# routev3_2.net
KiCad netlist of a schematic drawn in EAGLE
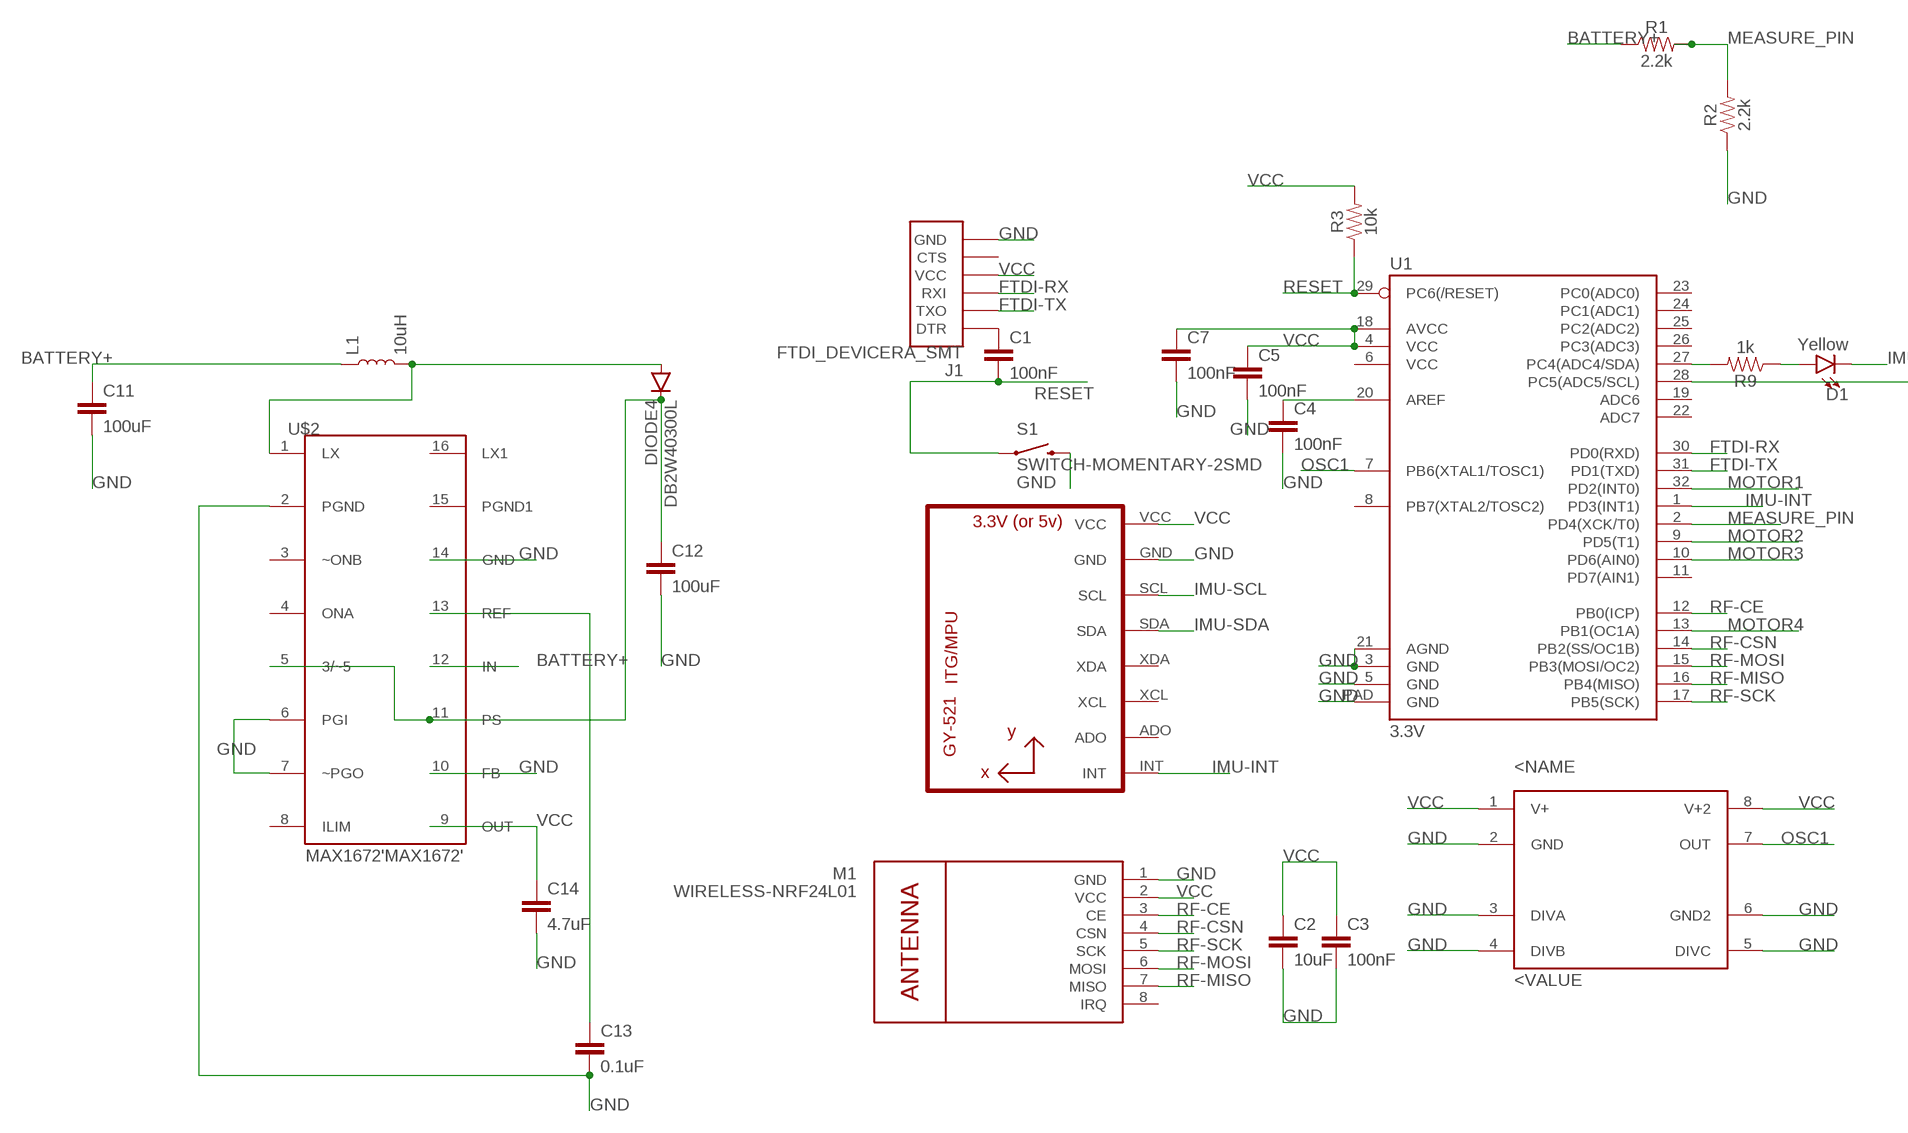
[diagram p0: schematic, sheet 1, part 1 of 2]
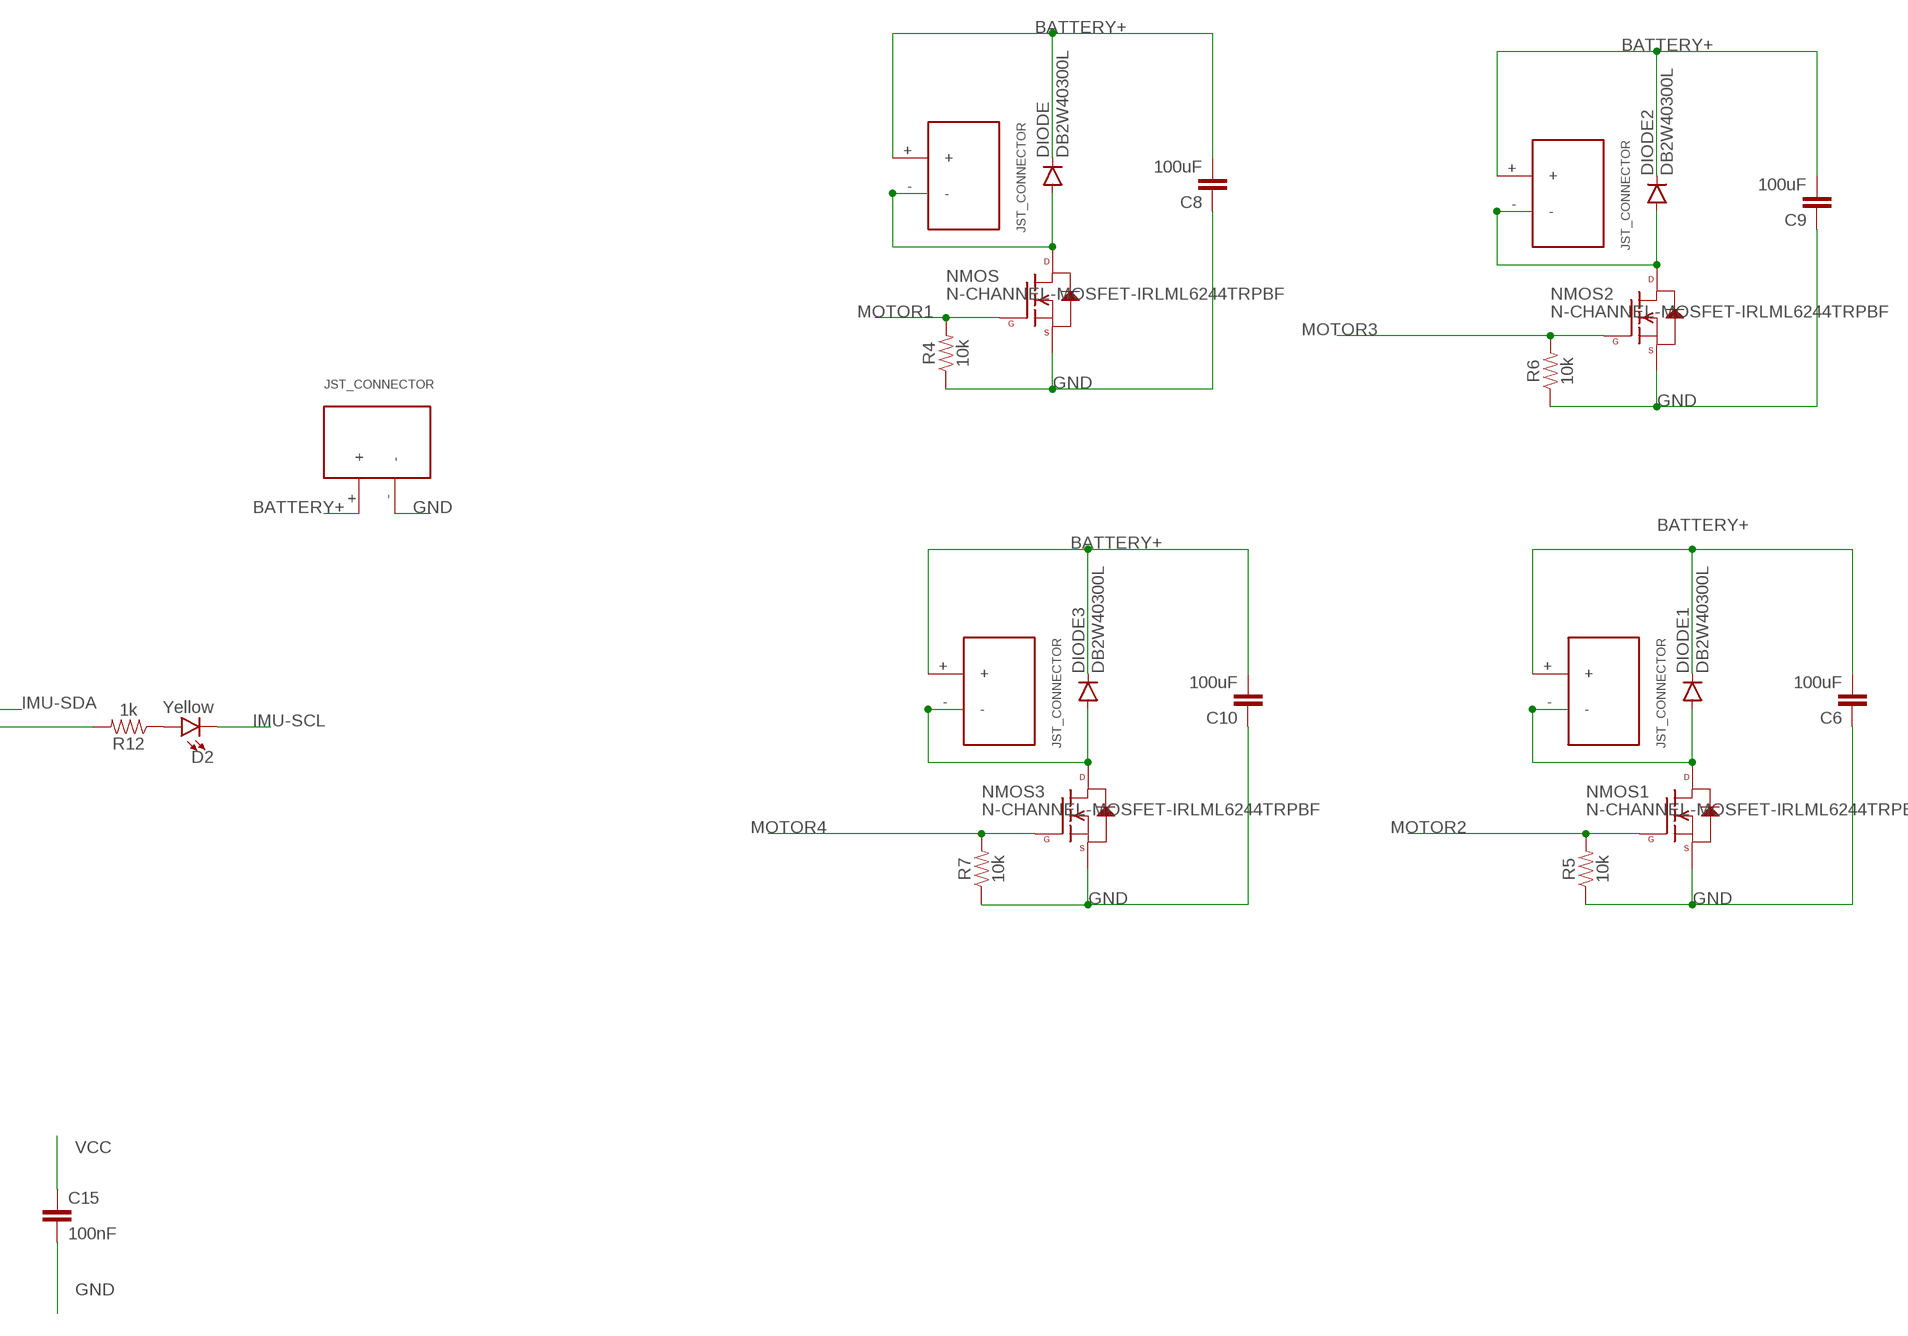
[diagram p1: schematic, sheet 1, part 2 of 2]

(export (version "E")
  (design (tool "Eeschema 10.0.6"))
  (components
    (comp (ref "C1")
      (value "100nF")
      (footprint "eagle-import:0603-CAP")
      (libsource (lib "eagle-import") (part "0.1UF-25V(+80/-20%)(0603)"))
    )
    (comp (ref "C2")
      (value "10uF")
      (footprint "eagle-import:0603-CAP")
      (libsource (lib "eagle-import") (part "CAP0603-CAP"))
    )
    (comp (ref "C3")
      (value "100nF")
      (footprint "eagle-import:0603-CAP")
      (libsource (lib "eagle-import") (part "CAP0603-CAP"))
    )
    (comp (ref "C4")
      (value "100nF")
      (footprint "eagle-import:0603-CAP")
      (libsource (lib "eagle-import") (part "CAP0603-CAP"))
    )
    (comp (ref "C5")
      (value "100nF")
      (footprint "eagle-import:0603-CAP")
      (libsource (lib "eagle-import") (part "CAP0603-CAP"))
    )
    (comp (ref "C6")
      (value "100uF")
      (footprint "eagle-import:0603-CAP")
      (libsource (lib "eagle-import") (part "CAP0603-CAP"))
    )
    (comp (ref "C7")
      (value "100nF")
      (footprint "eagle-import:0603-CAP")
      (libsource (lib "eagle-import") (part "CAP0603-CAP"))
    )
    (comp (ref "C8")
      (value "100uF")
      (footprint "eagle-import:0603-CAP")
      (libsource (lib "eagle-import") (part "CAP0603-CAP"))
    )
    (comp (ref "C9")
      (value "100uF")
      (footprint "eagle-import:0603-CAP")
      (libsource (lib "eagle-import") (part "CAP0603-CAP"))
    )
    (comp (ref "C10")
      (value "100uF")
      (footprint "eagle-import:0603-CAP")
      (libsource (lib "eagle-import") (part "CAP0603-CAP"))
    )
    (comp (ref "C11")
      (value "100uF")
      (footprint "eagle-import:0603-CAP")
      (libsource (lib "eagle-import") (part "CAP0603-CAP"))
    )
    (comp (ref "C12")
      (value "100uF")
      (footprint "eagle-import:0603-CAP")
      (libsource (lib "eagle-import") (part "CAP0603-CAP"))
    )
    (comp (ref "C13")
      (value "0.1uF")
      (footprint "eagle-import:0603-CAP")
      (libsource (lib "eagle-import") (part "CAP0603-CAP"))
    )
    (comp (ref "C14")
      (value "4.7uF")
      (footprint "eagle-import:0603-CAP")
      (libsource (lib "eagle-import") (part "CAP0603-CAP"))
    )
    (comp (ref "C15")
      (value "100nF")
      (footprint "eagle-import:0603-CAP")
      (libsource (lib "eagle-import") (part "0.1UF-25V(+80/-20%)(0603)"))
    )
    (comp (ref "D1")
      (value "Yellow")
      (footprint "eagle-import:LED-1206")
      (libsource (lib "eagle-import") (part "LED-YELLOWLILYPAD"))
    )
    (comp (ref "D2")
      (value "Yellow")
      (footprint "eagle-import:LED-1206")
      (libsource (lib "eagle-import") (part "LED-YELLOWLILYPAD"))
    )
    (comp (ref "DIODE")
      (value "DB2W40300L")
      (footprint "eagle-import:MINI2-F3-B")
      (libsource (lib "eagle-import") (part "DB2W40300L"))
    )
    (comp (ref "DIODE1")
      (value "DB2W40300L")
      (footprint "eagle-import:MINI2-F3-B")
      (libsource (lib "eagle-import") (part "DB2W40300L"))
    )
    (comp (ref "DIODE2")
      (value "DB2W40300L")
      (footprint "eagle-import:MINI2-F3-B")
      (libsource (lib "eagle-import") (part "DB2W40300L"))
    )
    (comp (ref "DIODE3")
      (value "DB2W40300L")
      (footprint "eagle-import:MINI2-F3-B")
      (libsource (lib "eagle-import") (part "DB2W40300L"))
    )
    (comp (ref "DIODE4")
      (value "DB2W40300L")
      (footprint "eagle-import:MINI2-F3-B")
      (libsource (lib "eagle-import") (part "DB2W40300L"))
    )
    (comp (ref "J1")
      (value "FTDI_DEVICERA_SMT")
      (footprint "eagle-import:FTDI_DEVICE_RA_SMT")
      (libsource (lib "eagle-import") (part "FTDI_DEVICERA_SMT"))
    )
    (comp (ref "L1")
      (value "10uH")
      (footprint "eagle-import:0603")
      (libsource (lib "eagle-import") (part "INDUCTOR-0603-33NH"))
    )
    (comp (ref "M1")
      (value "WIRELESS-NRF24L01")
      (footprint "eagle-import:WIRELESS-NRF24L01")
      (libsource (lib "eagle-import") (part "WIRELESS-NRF24L01"))
    )
    (comp (ref "MOTOR")
      (value "JST_CONNECTOR_FEMALE")
      (footprint "eagle-import:JST_CONNECTOR_FEMALE")
      (libsource (lib "eagle-import") (part "JST_CONNECTOR_FEMALE"))
    )
    (comp (ref "MOTOR1")
      (value "JST_CONNECTOR_FEMALE")
      (footprint "eagle-import:JST_CONNECTOR_FEMALE")
      (libsource (lib "eagle-import") (part "JST_CONNECTOR_FEMALE"))
    )
    (comp (ref "MOTOR2")
      (value "JST_CONNECTOR_FEMALE")
      (footprint "eagle-import:JST_CONNECTOR_FEMALE")
      (libsource (lib "eagle-import") (part "JST_CONNECTOR_FEMALE"))
    )
    (comp (ref "MOTOR3")
      (value "JST_CONNECTOR_FEMALE")
      (footprint "eagle-import:JST_CONNECTOR_FEMALE")
      (libsource (lib "eagle-import") (part "JST_CONNECTOR_FEMALE"))
    )
    (comp (ref "NMOS")
      (value "N-CHANNEL-MOSFET-IRLML6244TRPBF")
      (footprint "eagle-import:SOT23-3")
      (libsource (lib "eagle-import") (part "N-CHANNEL-MOSFET-IRLML6244TRPBF"))
    )
    (comp (ref "NMOS1")
      (value "N-CHANNEL-MOSFET-IRLML6244TRPBF")
      (footprint "eagle-import:SOT23-3")
      (libsource (lib "eagle-import") (part "N-CHANNEL-MOSFET-IRLML6244TRPBF"))
    )
    (comp (ref "NMOS2")
      (value "N-CHANNEL-MOSFET-IRLML6244TRPBF")
      (footprint "eagle-import:SOT23-3")
      (libsource (lib "eagle-import") (part "N-CHANNEL-MOSFET-IRLML6244TRPBF"))
    )
    (comp (ref "NMOS3")
      (value "N-CHANNEL-MOSFET-IRLML6244TRPBF")
      (footprint "eagle-import:SOT23-3")
      (libsource (lib "eagle-import") (part "N-CHANNEL-MOSFET-IRLML6244TRPBF"))
    )
    (comp (ref "R1")
      (value "2.2k")
      (footprint "eagle-import:0603")
      (libsource (lib "eagle-import") (part "2.2KOHM-0603-1/10W-1%"))
    )
    (comp (ref "R2")
      (value "2.2k")
      (footprint "eagle-import:0603")
      (libsource (lib "eagle-import") (part "2.2KOHM-0603-1/10W-1%"))
    )
    (comp (ref "R3")
      (value "10k")
      (footprint "eagle-import:0603")
      (libsource (lib "eagle-import") (part "2.2KOHM-0603-1/10W-1%"))
    )
    (comp (ref "R4")
      (value "10k")
      (footprint "eagle-import:0603")
      (libsource (lib "eagle-import") (part "2.2KOHM-0603-1/10W-1%"))
    )
    (comp (ref "R5")
      (value "10k")
      (footprint "eagle-import:0603")
      (libsource (lib "eagle-import") (part "2.2KOHM-0603-1/10W-1%"))
    )
    (comp (ref "R6")
      (value "10k")
      (footprint "eagle-import:0603")
      (libsource (lib "eagle-import") (part "2.2KOHM-0603-1/10W-1%"))
    )
    (comp (ref "R7")
      (value "10k")
      (footprint "eagle-import:0603")
      (libsource (lib "eagle-import") (part "2.2KOHM-0603-1/10W-1%"))
    )
    (comp (ref "R9")
      (value "1k")
      (footprint "eagle-import:0603")
      (libsource (lib "eagle-import") (part "2.2KOHM-0603-1/10W-1%"))
    )
    (comp (ref "R12")
      (value "1k")
      (footprint "eagle-import:0603")
      (libsource (lib "eagle-import") (part "2.2KOHM-0603-1/10W-1%"))
    )
    (comp (ref "S1")
      (value "SWITCH-MOMENTARY-2SMD")
      (footprint "eagle-import:TACTILE-SWITCH-SMD")
      (libsource (lib "eagle-import") (part "SWITCH-MOMENTARY-2SMD"))
    )
    (comp (ref "U$1")
      (value "JST_CONNECTOR_FEMALE")
      (footprint "eagle-import:JST_CONNECTOR_FEMALE")
      (libsource (lib "eagle-import") (part "JST_CONNECTOR_FEMALE"))
    )
    (comp (ref "U$2")
      (value "MAX1672'MAX1672'")
      (footprint "eagle-import:21-0055H_16")
      (libsource (lib "eagle-import") (part "MAX1672'MAX1672'"))
    )
    (comp (ref "U$3")
      (value "LTC6930CMS8-8.19LTC6930CMS8-8.19")
      (footprint "eagle-import:SOP65P490X110-8N")
      (libsource (lib "eagle-import") (part "LTC6930CMS8-8.19LTC6930CMS8-8.19"))
    )
    (comp (ref "U1")
      (value "3.3V")
      (footprint "eagle-import:MLF32-PAD")
      (libsource (lib "eagle-import") (part "ATMEGA328P_MLFMLF32"))
    )
    (comp (ref "U2")
      (value "GY-521MPU6050")
      (footprint "eagle-import:GY-521")
      (libsource (lib "eagle-import") (part "GY-521MPU6050"))
    )
  )
  (nets
    (net (code "1") (name "BATTERY+") (class "Default")
      (node (ref "C10") (pin "2") (pinfunction "2_2") (pintype "passive"))
      (node (ref "C11") (pin "1") (pinfunction "1_1") (pintype "passive"))
      (node (ref "C6") (pin "2") (pinfunction "2_2") (pintype "passive"))
      (node (ref "C8") (pin "2") (pinfunction "2_2") (pintype "passive"))
      (node (ref "C9") (pin "2") (pinfunction "2_2") (pintype "passive"))
      (node (ref "DIODE") (pin "NEG") (pinfunction "GPIN_NEG") (pintype "passive"))
      (node (ref "DIODE1") (pin "NEG") (pinfunction "GPIN_NEG") (pintype "passive"))
      (node (ref "DIODE2") (pin "NEG") (pinfunction "GPIN_NEG") (pintype "passive"))
      (node (ref "DIODE3") (pin "NEG") (pinfunction "GPIN_NEG") (pintype "passive"))
      (node (ref "L1") (pin "1") (pinfunction "1_1") (pintype "passive"))
      (node (ref "MOTOR") (pin "+") (pinfunction "+_+") (pintype "bidirectional"))
      (node (ref "MOTOR1") (pin "+") (pinfunction "+_+") (pintype "bidirectional"))
      (node (ref "MOTOR2") (pin "+") (pinfunction "+_+") (pintype "bidirectional"))
      (node (ref "MOTOR3") (pin "+") (pinfunction "+_+") (pintype "bidirectional"))
      (node (ref "R1") (pin "1") (pinfunction "1_1") (pintype "passive"))
      (node (ref "U$1") (pin "+") (pinfunction "+_+") (pintype "bidirectional"))
      (node (ref "U$2") (pin "12") (pinfunction "IN_12") (pintype "bidirectional"))
    )
    (net (code "2") (name "FTDI-RX") (class "Default")
      (node (ref "J1") (pin "3") (pinfunction "RXI_3") (pintype "bidirectional"))
      (node (ref "U1") (pin "30") (pinfunction "PD0(RXD)_30") (pintype "bidirectional"))
    )
    (net (code "3") (name "FTDI-TX") (class "Default")
      (node (ref "J1") (pin "2") (pinfunction "TXO_2") (pintype "bidirectional"))
      (node (ref "U1") (pin "31") (pinfunction "PD1(TXD)_31") (pintype "bidirectional"))
    )
    (net (code "4") (name "GND") (class "Default")
      (node (ref "C10") (pin "1") (pinfunction "1_1") (pintype "passive"))
      (node (ref "C11") (pin "2") (pinfunction "2_2") (pintype "passive"))
      (node (ref "C12") (pin "2") (pinfunction "2_2") (pintype "passive"))
      (node (ref "C13") (pin "2") (pinfunction "2_2") (pintype "passive"))
      (node (ref "C14") (pin "2") (pinfunction "2_2") (pintype "passive"))
      (node (ref "C15") (pin "2") (pinfunction "2_2") (pintype "passive"))
      (node (ref "C2") (pin "2") (pinfunction "2_2") (pintype "passive"))
      (node (ref "C3") (pin "2") (pinfunction "2_2") (pintype "passive"))
      (node (ref "C4") (pin "2") (pinfunction "2_2") (pintype "passive"))
      (node (ref "C5") (pin "2") (pinfunction "2_2") (pintype "passive"))
      (node (ref "C6") (pin "1") (pinfunction "1_1") (pintype "passive"))
      (node (ref "C7") (pin "2") (pinfunction "2_2") (pintype "passive"))
      (node (ref "C8") (pin "1") (pinfunction "1_1") (pintype "passive"))
      (node (ref "C9") (pin "1") (pinfunction "1_1") (pintype "passive"))
      (node (ref "J1") (pin "6") (pinfunction "GND_6") (pintype "bidirectional"))
      (node (ref "M1") (pin "1") (pinfunction "GND_1") (pintype "power_in"))
      (node (ref "NMOS") (pin "2") (pinfunction "S_2") (pintype "passive"))
      (node (ref "NMOS1") (pin "2") (pinfunction "S_2") (pintype "passive"))
      (node (ref "NMOS2") (pin "2") (pinfunction "S_2") (pintype "passive"))
      (node (ref "NMOS3") (pin "2") (pinfunction "S_2") (pintype "passive"))
      (node (ref "R2") (pin "1") (pinfunction "1_1") (pintype "passive"))
      (node (ref "R4") (pin "1") (pinfunction "1_1") (pintype "passive"))
      (node (ref "R5") (pin "1") (pinfunction "1_1") (pintype "passive"))
      (node (ref "R6") (pin "1") (pinfunction "1_1") (pintype "passive"))
      (node (ref "R7") (pin "1") (pinfunction "1_1") (pintype "passive"))
      (node (ref "S1") (pin "3") (pinfunction "2_3") (pintype "passive"))
      (node (ref "U$1") (pin "-") (pinfunction "-_-") (pintype "bidirectional"))
      (node (ref "U$2") (pin "10") (pinfunction "FB_10") (pintype "bidirectional"))
      (node (ref "U$2") (pin "14") (pinfunction "GND_14") (pintype "bidirectional"))
      (node (ref "U$2") (pin "2") (pinfunction "PGND_2") (pintype "bidirectional"))
      (node (ref "U$2") (pin "6") (pinfunction "PGI_6") (pintype "bidirectional"))
      (node (ref "U$2") (pin "7") (pinfunction "~{PGO}_7") (pintype "bidirectional"))
      (node (ref "U$3") (pin "2") (pinfunction "GND_2") (pintype "bidirectional"))
      (node (ref "U$3") (pin "3") (pinfunction "DIVA_3") (pintype "bidirectional"))
      (node (ref "U$3") (pin "4") (pinfunction "DIVB_4") (pintype "bidirectional"))
      (node (ref "U$3") (pin "5") (pinfunction "DIVC_5") (pintype "bidirectional"))
      (node (ref "U$3") (pin "6") (pinfunction "GND2_6") (pintype "bidirectional"))
      (node (ref "U1") (pin "21") (pinfunction "AGND_21") (pintype "bidirectional"))
      (node (ref "U1") (pin "3") (pinfunction "GND_3") (pintype "bidirectional"))
      (node (ref "U1") (pin "5") (pinfunction "GND_5") (pintype "bidirectional"))
      (node (ref "U1") (pin "PAD") (pinfunction "GND_PAD") (pintype "bidirectional"))
      (node (ref "U2") (pin "GND") (pinfunction "GND_GND") (pintype "bidirectional"))
    )
    (net (code "5") (name "IMU-INT") (class "Default")
      (node (ref "U1") (pin "1") (pinfunction "PD3(INT1)_1") (pintype "bidirectional"))
      (node (ref "U2") (pin "INT") (pinfunction "INT_INT") (pintype "bidirectional"))
    )
    (net (code "6") (name "IMU-SCL") (class "Default")
      (node (ref "D2") (pin "C") (pinfunction "C_C") (pintype "passive"))
      (node (ref "U2") (pin "SCL") (pinfunction "SCL_SCL") (pintype "bidirectional"))
    )
    (net (code "7") (name "IMU-SDA") (class "Default")
      (node (ref "D1") (pin "C") (pinfunction "C_C") (pintype "passive"))
      (node (ref "U2") (pin "SDA") (pinfunction "SDA_SDA") (pintype "bidirectional"))
    )
    (net (code "8") (name "MEASURE_PIN") (class "Default")
      (node (ref "R1") (pin "2") (pinfunction "2_2") (pintype "passive"))
      (node (ref "R2") (pin "2") (pinfunction "2_2") (pintype "passive"))
      (node (ref "U1") (pin "2") (pinfunction "PD4(XCK/T0)_2") (pintype "bidirectional"))
    )
    (net (code "9") (name "MOTOR1") (class "Default")
      (node (ref "NMOS") (pin "1") (pinfunction "G_1") (pintype "passive"))
      (node (ref "R4") (pin "2") (pinfunction "2_2") (pintype "passive"))
      (node (ref "U1") (pin "32") (pinfunction "PD2(INT0)_32") (pintype "bidirectional"))
    )
    (net (code "10") (name "MOTOR2") (class "Default")
      (node (ref "NMOS1") (pin "1") (pinfunction "G_1") (pintype "passive"))
      (node (ref "R5") (pin "2") (pinfunction "2_2") (pintype "passive"))
      (node (ref "U1") (pin "9") (pinfunction "PD5(T1)_9") (pintype "bidirectional"))
    )
    (net (code "11") (name "MOTOR3") (class "Default")
      (node (ref "NMOS2") (pin "1") (pinfunction "G_1") (pintype "passive"))
      (node (ref "R6") (pin "2") (pinfunction "2_2") (pintype "passive"))
      (node (ref "U1") (pin "10") (pinfunction "PD6(AIN0)_10") (pintype "bidirectional"))
    )
    (net (code "12") (name "MOTOR4") (class "Default")
      (node (ref "NMOS3") (pin "1") (pinfunction "G_1") (pintype "passive"))
      (node (ref "R7") (pin "2") (pinfunction "2_2") (pintype "passive"))
      (node (ref "U1") (pin "13") (pinfunction "PB1(OC1A)_13") (pintype "bidirectional"))
    )
    (net (code "13") (name "Net-(D1-PadA)") (class "Default")
      (node (ref "D1") (pin "A") (pinfunction "A_A") (pintype "passive"))
      (node (ref "R9") (pin "1") (pinfunction "1_1") (pintype "passive"))
    )
    (net (code "14") (name "Net-(D2-PadA)") (class "Default")
      (node (ref "D2") (pin "A") (pinfunction "A_A") (pintype "passive"))
      (node (ref "R12") (pin "1") (pinfunction "1_1") (pintype "passive"))
    )
    (net (code "15") (name "Net-(DIODE-PPIN)") (class "Default")
      (node (ref "DIODE") (pin "POS") (pinfunction "PPIN_POS") (pintype "passive"))
      (node (ref "MOTOR") (pin "-") (pinfunction "-_-") (pintype "bidirectional"))
      (node (ref "NMOS") (pin "3") (pinfunction "D_3") (pintype "passive"))
    )
    (net (code "16") (name "Net-(DIODE1-PPIN)") (class "Default")
      (node (ref "DIODE1") (pin "POS") (pinfunction "PPIN_POS") (pintype "passive"))
      (node (ref "MOTOR1") (pin "-") (pinfunction "-_-") (pintype "bidirectional"))
      (node (ref "NMOS1") (pin "3") (pinfunction "D_3") (pintype "passive"))
    )
    (net (code "17") (name "Net-(DIODE2-PPIN)") (class "Default")
      (node (ref "DIODE2") (pin "POS") (pinfunction "PPIN_POS") (pintype "passive"))
      (node (ref "MOTOR2") (pin "-") (pinfunction "-_-") (pintype "bidirectional"))
      (node (ref "NMOS2") (pin "3") (pinfunction "D_3") (pintype "passive"))
    )
    (net (code "18") (name "Net-(DIODE3-PPIN)") (class "Default")
      (node (ref "DIODE3") (pin "POS") (pinfunction "PPIN_POS") (pintype "passive"))
      (node (ref "MOTOR3") (pin "-") (pinfunction "-_-") (pintype "bidirectional"))
      (node (ref "NMOS3") (pin "3") (pinfunction "D_3") (pintype "passive"))
    )
    (net (code "19") (name "Net-(DIODE4-GPIN)") (class "Default")
      (node (ref "C12") (pin "1") (pinfunction "1_1") (pintype "passive"))
      (node (ref "DIODE4") (pin "NEG") (pinfunction "GPIN_NEG") (pintype "passive"))
      (node (ref "U$2") (pin "11") (pinfunction "PS_11") (pintype "bidirectional"))
      (node (ref "U$2") (pin "5") (pinfunction "3/~{5}_5") (pintype "bidirectional"))
    )
    (net (code "20") (name "Net-(DIODE4-PPIN)") (class "Default")
      (node (ref "DIODE4") (pin "POS") (pinfunction "PPIN_POS") (pintype "passive"))
      (node (ref "L1") (pin "2") (pinfunction "2_2") (pintype "passive"))
      (node (ref "U$2") (pin "1") (pinfunction "LX_1") (pintype "bidirectional"))
    )
    (net (code "21") (name "Net-(J1-DTR)") (class "Default")
      (node (ref "C1") (pin "1") (pinfunction "1_1") (pintype "passive"))
      (node (ref "J1") (pin "1") (pinfunction "DTR_1") (pintype "bidirectional"))
    )
    (net (code "22") (name "Net-(U$2-REF)") (class "Default")
      (node (ref "C13") (pin "1") (pinfunction "1_1") (pintype "passive"))
      (node (ref "U$2") (pin "13") (pinfunction "REF_13") (pintype "bidirectional"))
    )
    (net (code "23") (name "Net-(U1-AREF)") (class "Default")
      (node (ref "C4") (pin "1") (pinfunction "1_1") (pintype "passive"))
      (node (ref "U1") (pin "20") (pinfunction "AREF_20") (pintype "bidirectional"))
    )
    (net (code "24") (name "Net-(U1-PC4(ADC4{slash}SDA))") (class "Default")
      (node (ref "R9") (pin "2") (pinfunction "2_2") (pintype "passive"))
      (node (ref "U1") (pin "27") (pinfunction "PC4(ADC4/SDA)_27") (pintype "bidirectional"))
    )
    (net (code "25") (name "Net-(U1-PC5(ADC5{slash}SCL))") (class "Default")
      (node (ref "R12") (pin "2") (pinfunction "2_2") (pintype "passive"))
      (node (ref "U1") (pin "28") (pinfunction "PC5(ADC5/SCL)_28") (pintype "bidirectional"))
    )
    (net (code "26") (name "OSC1") (class "Default")
      (node (ref "U$3") (pin "7") (pinfunction "OUT_7") (pintype "bidirectional"))
      (node (ref "U1") (pin "7") (pinfunction "PB6(XTAL1/TOSC1)_7") (pintype "bidirectional"))
    )
    (net (code "27") (name "RESET") (class "Default")
      (node (ref "C1") (pin "2") (pinfunction "2_2") (pintype "passive"))
      (node (ref "R3") (pin "1") (pinfunction "1_1") (pintype "passive"))
      (node (ref "S1") (pin "1") (pinfunction "1_1") (pintype "passive"))
      (node (ref "U1") (pin "29") (pinfunction "PC6(/RESET)_29") (pintype "bidirectional"))
    )
    (net (code "28") (name "RF-CE") (class "Default")
      (node (ref "M1") (pin "3") (pinfunction "CE_3") (pintype "bidirectional"))
      (node (ref "U1") (pin "12") (pinfunction "PB0(ICP)_12") (pintype "bidirectional"))
    )
    (net (code "29") (name "RF-CSN") (class "Default")
      (node (ref "M1") (pin "4") (pinfunction "CSN_4") (pintype "bidirectional"))
      (node (ref "U1") (pin "14") (pinfunction "PB2(SS/OC1B)_14") (pintype "bidirectional"))
    )
    (net (code "30") (name "RF-MISO") (class "Default")
      (node (ref "M1") (pin "7") (pinfunction "MISO_7") (pintype "bidirectional"))
      (node (ref "U1") (pin "16") (pinfunction "PB4(MISO)_16") (pintype "bidirectional"))
    )
    (net (code "31") (name "RF-MOSI") (class "Default")
      (node (ref "M1") (pin "6") (pinfunction "MOSI_6") (pintype "bidirectional"))
      (node (ref "U1") (pin "15") (pinfunction "PB3(MOSI/OC2)_15") (pintype "bidirectional"))
    )
    (net (code "32") (name "RF-SCK") (class "Default")
      (node (ref "M1") (pin "5") (pinfunction "SCK_5") (pintype "bidirectional"))
      (node (ref "U1") (pin "17") (pinfunction "PB5(SCK)_17") (pintype "bidirectional"))
    )
    (net (code "33") (name "VCC") (class "Default")
      (node (ref "C14") (pin "1") (pinfunction "1_1") (pintype "passive"))
      (node (ref "C15") (pin "1") (pinfunction "1_1") (pintype "passive"))
      (node (ref "C2") (pin "1") (pinfunction "1_1") (pintype "passive"))
      (node (ref "C3") (pin "1") (pinfunction "1_1") (pintype "passive"))
      (node (ref "C5") (pin "1") (pinfunction "1_1") (pintype "passive"))
      (node (ref "C7") (pin "1") (pinfunction "1_1") (pintype "passive"))
      (node (ref "J1") (pin "4") (pinfunction "VCC_4") (pintype "bidirectional"))
      (node (ref "M1") (pin "2") (pinfunction "VCC_2") (pintype "power_in"))
      (node (ref "R3") (pin "2") (pinfunction "2_2") (pintype "passive"))
      (node (ref "U$2") (pin "9") (pinfunction "OUT_9") (pintype "bidirectional"))
      (node (ref "U$3") (pin "1") (pinfunction "V+_1") (pintype "bidirectional"))
      (node (ref "U$3") (pin "8") (pinfunction "V+2_8") (pintype "bidirectional"))
      (node (ref "U1") (pin "18") (pinfunction "AVCC_18") (pintype "bidirectional"))
      (node (ref "U1") (pin "4") (pinfunction "VCC_4") (pintype "bidirectional"))
      (node (ref "U2") (pin "VCC") (pinfunction "VCC_VCC") (pintype "bidirectional"))
    )
    (net (code "34") (name "unconnected-(J1-CTS-Pad5)") (class "Default")
      (node (ref "J1") (pin "5") (pinfunction "CTS_5") (pintype "bidirectional"))
    )
    (net (code "35") (name "unconnected-(M1-IRQ-Pad8)") (class "Default")
      (node (ref "M1") (pin "8") (pinfunction "IRQ_8") (pintype "bidirectional"))
    )
    (net (code "36") (name "unconnected-(U$2-ILIM-Pad8)") (class "Default")
      (node (ref "U$2") (pin "8") (pinfunction "ILIM_8") (pintype "bidirectional"))
    )
    (net (code "37") (name "unconnected-(U$2-LX1-Pad16)") (class "Default")
      (node (ref "U$2") (pin "16") (pinfunction "LX1_16") (pintype "bidirectional"))
    )
    (net (code "38") (name "unconnected-(U$2-ONA-Pad4)") (class "Default")
      (node (ref "U$2") (pin "4") (pinfunction "ONA_4") (pintype "bidirectional"))
    )
    (net (code "39") (name "unconnected-(U$2-PGND1-Pad15)") (class "Default")
      (node (ref "U$2") (pin "15") (pinfunction "PGND1_15") (pintype "bidirectional"))
    )
    (net (code "40") (name "unconnected-(U$2-~{ONB}-Pad3)") (class "Default")
      (node (ref "U$2") (pin "3") (pinfunction "~{ONB}_3") (pintype "bidirectional"))
    )
    (net (code "41") (name "unconnected-(U1-ADC6-Pad19)") (class "Default")
      (node (ref "U1") (pin "19") (pinfunction "ADC6_19") (pintype "bidirectional"))
    )
    (net (code "42") (name "unconnected-(U1-ADC7-Pad22)") (class "Default")
      (node (ref "U1") (pin "22") (pinfunction "ADC7_22") (pintype "bidirectional"))
    )
    (net (code "43") (name "unconnected-(U1-PB7(XTAL2{slash}TOSC2)-Pad8)") (class "Default")
      (node (ref "U1") (pin "8") (pinfunction "PB7(XTAL2/TOSC2)_8") (pintype "bidirectional"))
    )
    (net (code "44") (name "unconnected-(U1-PC0(ADC0)-Pad23)") (class "Default")
      (node (ref "U1") (pin "23") (pinfunction "PC0(ADC0)_23") (pintype "bidirectional"))
    )
    (net (code "45") (name "unconnected-(U1-PC1(ADC1)-Pad24)") (class "Default")
      (node (ref "U1") (pin "24") (pinfunction "PC1(ADC1)_24") (pintype "bidirectional"))
    )
    (net (code "46") (name "unconnected-(U1-PC2(ADC2)-Pad25)") (class "Default")
      (node (ref "U1") (pin "25") (pinfunction "PC2(ADC2)_25") (pintype "bidirectional"))
    )
    (net (code "47") (name "unconnected-(U1-PC3(ADC3)-Pad26)") (class "Default")
      (node (ref "U1") (pin "26") (pinfunction "PC3(ADC3)_26") (pintype "bidirectional"))
    )
    (net (code "48") (name "unconnected-(U1-PD7(AIN1)-Pad11)") (class "Default")
      (node (ref "U1") (pin "11") (pinfunction "PD7(AIN1)_11") (pintype "bidirectional"))
    )
    (net (code "49") (name "unconnected-(U1-VCC-Pad6)") (class "Default")
      (node (ref "U1") (pin "6") (pinfunction "VCC_6") (pintype "bidirectional"))
    )
    (net (code "50") (name "unconnected-(U2-PadADO)") (class "Default")
      (node (ref "U2") (pin "ADO") (pinfunction "ADO_ADO") (pintype "bidirectional"))
    )
    (net (code "51") (name "unconnected-(U2-PadXCL)") (class "Default")
      (node (ref "U2") (pin "XCL") (pinfunction "XCL_XCL") (pintype "bidirectional"))
    )
    (net (code "52") (name "unconnected-(U2-PadXDA)") (class "Default")
      (node (ref "U2") (pin "XDA") (pinfunction "XDA_XDA") (pintype "bidirectional"))
    )
  )
)
